# MRCS-Dual-3-Position-Semaphore-Controlle.net
KiCad netlist of a schematic drawn in EAGLE
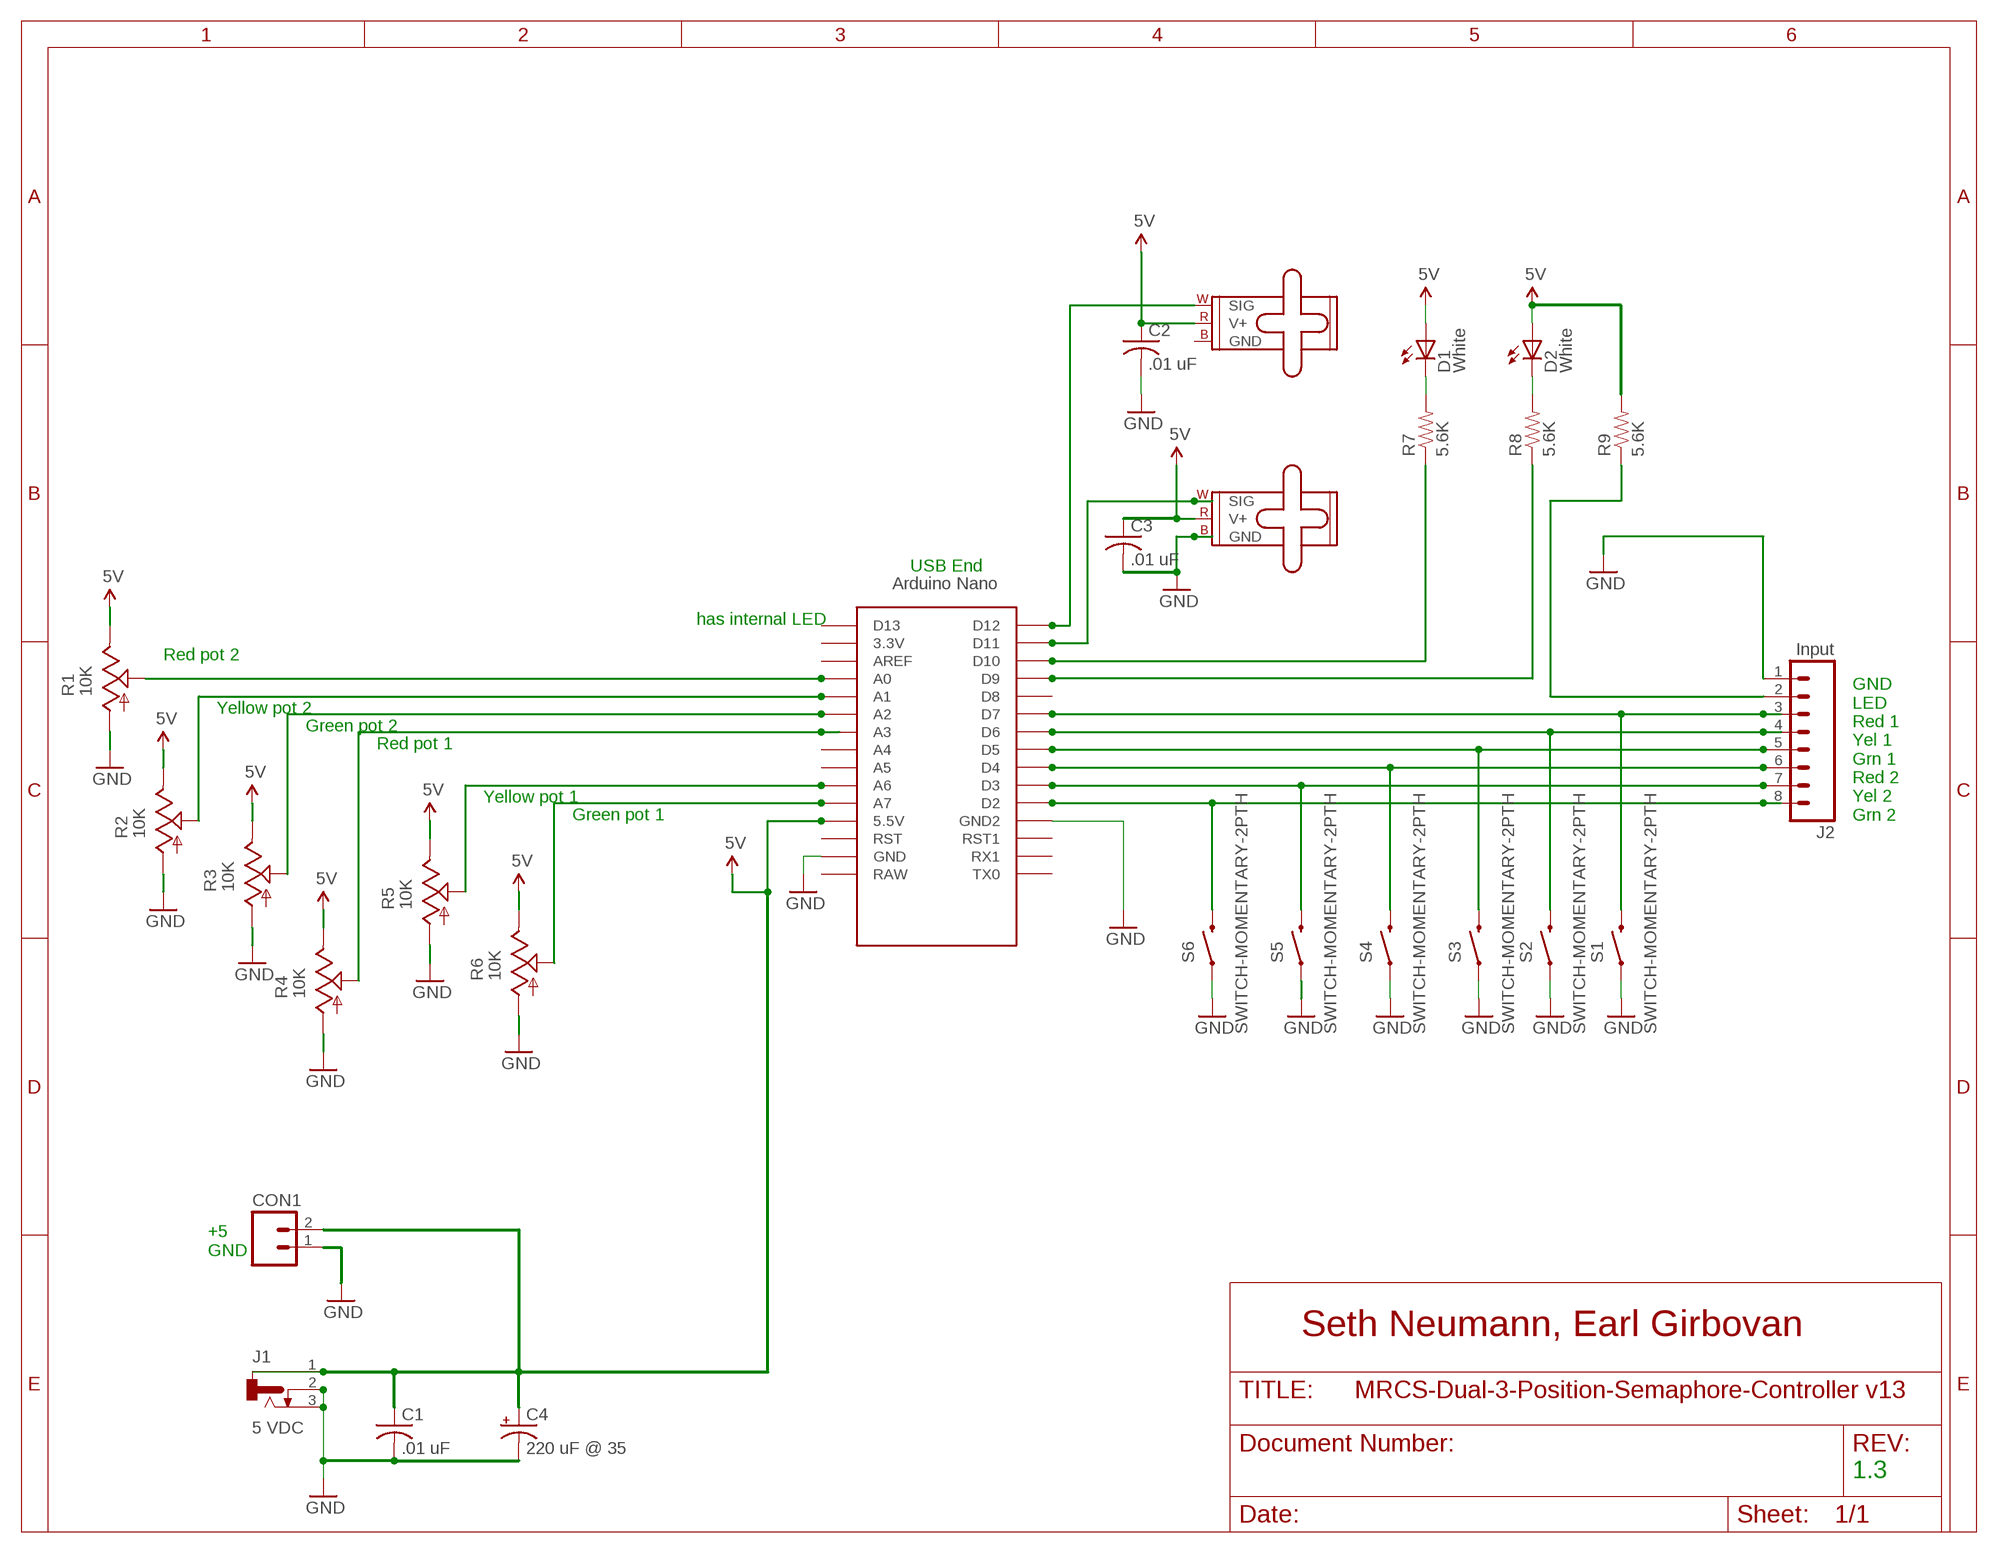
[diagram p0: schematic, sheet 1]

(export (version "E")
  (design (tool "Eeschema 10.0.6"))
  (components
    (comp (ref "C1")
      (value ".01 uF")
      (footprint "eagle-import:C050-024X044")
      (libsource (lib "eagle-import") (part "CAPPTH1"))
    )
    (comp (ref "C2")
      (value ".01 uF")
      (footprint "eagle-import:C050-024X044")
      (libsource (lib "eagle-import") (part "CAPPTH1"))
    )
    (comp (ref "C3")
      (value ".01 uF")
      (footprint "eagle-import:C050-024X044")
      (libsource (lib "eagle-import") (part "CAPPTH1"))
    )
    (comp (ref "C4")
      (value "220 uF @ 35")
      (footprint "eagle-import:E5-10.5")
      (libsource (lib "eagle-import") (part "CAP-POLPTH-5MM"))
    )
    (comp (ref "CON1")
      (value "CONNECTOR-M023.5MM-LOCK")
      (footprint "eagle-import:SCREWTERMINAL-3.5MM-2_LOCK")
      (libsource (lib "eagle-import") (part "CONNECTOR-M023.5MM-LOCK"))
    )
    (comp (ref "D1")
      (value "White")
      (footprint "eagle-import:LED3MM")
      (libsource (lib "eagle-import") (part "LEDLED3MM"))
    )
    (comp (ref "D2")
      (value "White")
      (footprint "eagle-import:LED3MM")
      (libsource (lib "eagle-import") (part "LEDLED3MM"))
    )
    (comp (ref "J1")
      (value "5 VDC")
      (footprint "eagle-import:DCJ0202")
      (libsource (lib "eagle-import") (part "CONNECTOR-DC-POWER-RA"))
    )
    (comp (ref "J2")
      (value "Input")
      (footprint "eagle-import:1X08_LOCK")
      (libsource (lib "eagle-import") (part "CONNECTOR-M08LOCK"))
    )
    (comp (ref "M1")
      (value "SMALL_SERVO")
      (footprint "eagle-import:1X03")
      (libsource (lib "eagle-import") (part "SMALL_SERVO"))
    )
    (comp (ref "M2")
      (value "SMALL_SERVO")
      (footprint "eagle-import:1X03")
      (libsource (lib "eagle-import") (part "SMALL_SERVO"))
    )
    (comp (ref "NANO")
      (value "NANO")
      (footprint "eagle-import:NANO")
      (libsource (lib "eagle-import") (part "NANO"))
    )
    (comp (ref "R1")
      (value "10K")
      (footprint "eagle-import:RS3")
      (libsource (lib "eagle-import") (part "TRIM_US-RS3"))
    )
    (comp (ref "R2")
      (value "10K")
      (footprint "eagle-import:RS3")
      (libsource (lib "eagle-import") (part "TRIM_US-RS3"))
    )
    (comp (ref "R3")
      (value "10K")
      (footprint "eagle-import:RS3")
      (libsource (lib "eagle-import") (part "TRIM_US-RS3"))
    )
    (comp (ref "R4")
      (value "10K")
      (footprint "eagle-import:RS3")
      (libsource (lib "eagle-import") (part "TRIM_US-RS3"))
    )
    (comp (ref "R5")
      (value "10K")
      (footprint "eagle-import:RS3")
      (libsource (lib "eagle-import") (part "TRIM_US-RS3"))
    )
    (comp (ref "R6")
      (value "10K")
      (footprint "eagle-import:RS3")
      (libsource (lib "eagle-import") (part "TRIM_US-RS3"))
    )
    (comp (ref "R7")
      (value "5.6K")
      (footprint "eagle-import:AXIAL-0.4")
      (libsource (lib "eagle-import") (part "RESISTORPTH-1/4W"))
    )
    (comp (ref "R8")
      (value "5.6K")
      (footprint "eagle-import:AXIAL-0.4")
      (libsource (lib "eagle-import") (part "RESISTORPTH-1/4W"))
    )
    (comp (ref "R9")
      (value "5.6K")
      (footprint "eagle-import:AXIAL-0.4")
      (libsource (lib "eagle-import") (part "RESISTORPTH-1/4W"))
    )
    (comp (ref "S1")
      (value "SWITCH-MOMENTARY-2PTH")
      (footprint "eagle-import:TACTILE-PTH")
      (libsource (lib "eagle-import") (part "SWITCH-MOMENTARY-2PTH"))
    )
    (comp (ref "S2")
      (value "SWITCH-MOMENTARY-2PTH")
      (footprint "eagle-import:TACTILE-PTH")
      (libsource (lib "eagle-import") (part "SWITCH-MOMENTARY-2PTH"))
    )
    (comp (ref "S3")
      (value "SWITCH-MOMENTARY-2PTH")
      (footprint "eagle-import:TACTILE-PTH")
      (libsource (lib "eagle-import") (part "SWITCH-MOMENTARY-2PTH"))
    )
    (comp (ref "S4")
      (value "SWITCH-MOMENTARY-2PTH")
      (footprint "eagle-import:TACTILE-PTH")
      (libsource (lib "eagle-import") (part "SWITCH-MOMENTARY-2PTH"))
    )
    (comp (ref "S5")
      (value "SWITCH-MOMENTARY-2PTH")
      (footprint "eagle-import:TACTILE-PTH")
      (libsource (lib "eagle-import") (part "SWITCH-MOMENTARY-2PTH"))
    )
    (comp (ref "S6")
      (value "SWITCH-MOMENTARY-2PTH")
      (footprint "eagle-import:TACTILE-PTH")
      (libsource (lib "eagle-import") (part "SWITCH-MOMENTARY-2PTH"))
    )
  )
  (nets
    (net (code "1") (name "5V") (class "Default")
      (node (ref "C1") (pin "1") (pinfunction "1_1") (pintype "passive"))
      (node (ref "C2") (pin "1") (pinfunction "1_1") (pintype "passive"))
      (node (ref "C3") (pin "1") (pinfunction "1_1") (pintype "passive"))
      (node (ref "C4") (pin "+") (pinfunction "+_+") (pintype "passive"))
      (node (ref "CON1") (pin "2") (pinfunction "B_2") (pintype "passive"))
      (node (ref "D1") (pin "A") (pinfunction "A_A") (pintype "passive"))
      (node (ref "D2") (pin "A") (pinfunction "A_A") (pintype "passive"))
      (node (ref "J1") (pin "1") (pinfunction "1_1") (pintype "passive"))
      (node (ref "M1") (pin "2") (pinfunction "V+_2") (pintype "bidirectional"))
      (node (ref "M2") (pin "2") (pinfunction "V+_2") (pintype "bidirectional"))
      (node (ref "NANO") (pin "5V") (pinfunction "5.5V_5V") (pintype "bidirectional"))
      (node (ref "R1") (pin "E") (pinfunction "E_E") (pintype "passive"))
      (node (ref "R2") (pin "E") (pinfunction "E_E") (pintype "passive"))
      (node (ref "R3") (pin "E") (pinfunction "E_E") (pintype "passive"))
      (node (ref "R4") (pin "E") (pinfunction "E_E") (pintype "passive"))
      (node (ref "R5") (pin "E") (pinfunction "E_E") (pintype "passive"))
      (node (ref "R6") (pin "E") (pinfunction "E_E") (pintype "passive"))
      (node (ref "R9") (pin "P$2") (pinfunction "2_P$2") (pintype "passive"))
    )
    (net (code "2") (name "GND") (class "Default")
      (node (ref "C1") (pin "2") (pinfunction "2_2") (pintype "passive"))
      (node (ref "C2") (pin "2") (pinfunction "2_2") (pintype "passive"))
      (node (ref "C3") (pin "2") (pinfunction "2_2") (pintype "passive"))
      (node (ref "C4") (pin "-") (pinfunction "-_-") (pintype "passive"))
      (node (ref "CON1") (pin "1") (pinfunction "A_1") (pintype "passive"))
      (node (ref "J1") (pin "2") (pinfunction "2_2") (pintype "passive"))
      (node (ref "J1") (pin "3") (pinfunction "3_3") (pintype "passive"))
      (node (ref "J2") (pin "1") (pinfunction "1_1") (pintype "passive"))
      (node (ref "M2") (pin "3") (pinfunction "GND_3") (pintype "bidirectional"))
      (node (ref "NANO") (pin "GND") (pinfunction "GND_GND") (pintype "bidirectional"))
      (node (ref "NANO") (pin "GND1") (pinfunction "GND2_GND1") (pintype "bidirectional"))
      (node (ref "R1") (pin "A") (pinfunction "A_A") (pintype "passive"))
      (node (ref "R2") (pin "A") (pinfunction "A_A") (pintype "passive"))
      (node (ref "R3") (pin "A") (pinfunction "A_A") (pintype "passive"))
      (node (ref "R4") (pin "A") (pinfunction "A_A") (pintype "passive"))
      (node (ref "R5") (pin "A") (pinfunction "A_A") (pintype "passive"))
      (node (ref "R6") (pin "A") (pinfunction "A_A") (pintype "passive"))
      (node (ref "S1") (pin "1") (pinfunction "1_1") (pintype "passive"))
      (node (ref "S2") (pin "1") (pinfunction "1_1") (pintype "passive"))
      (node (ref "S3") (pin "1") (pinfunction "1_1") (pintype "passive"))
      (node (ref "S4") (pin "1") (pinfunction "1_1") (pintype "passive"))
      (node (ref "S5") (pin "1") (pinfunction "1_1") (pintype "passive"))
      (node (ref "S6") (pin "1") (pinfunction "1_1") (pintype "passive"))
    )
    (net (code "3") (name "Net-(D1-C)") (class "Default")
      (node (ref "D1") (pin "K") (pinfunction "C_K") (pintype "passive"))
      (node (ref "R7") (pin "P$2") (pinfunction "2_P$2") (pintype "passive"))
    )
    (net (code "4") (name "Net-(D2-C)") (class "Default")
      (node (ref "D2") (pin "K") (pinfunction "C_K") (pintype "passive"))
      (node (ref "R8") (pin "P$2") (pinfunction "2_P$2") (pintype "passive"))
    )
    (net (code "5") (name "Net-(M1-SIG)") (class "Default")
      (node (ref "M1") (pin "1") (pinfunction "SIG_1") (pintype "bidirectional"))
      (node (ref "NANO") (pin "D12") (pinfunction "D12_D12") (pintype "bidirectional"))
    )
    (net (code "6") (name "Net-(M2-SIG)") (class "Default")
      (node (ref "M2") (pin "1") (pinfunction "SIG_1") (pintype "bidirectional"))
      (node (ref "NANO") (pin "D11") (pinfunction "D11_D11") (pintype "bidirectional"))
    )
    (net (code "7") (name "Net-(NANO-PadA0)") (class "Default")
      (node (ref "NANO") (pin "A0") (pinfunction "A0_A0") (pintype "bidirectional"))
      (node (ref "R1") (pin "S") (pinfunction "S_S") (pintype "passive"))
    )
    (net (code "8") (name "Net-(NANO-PadA1)") (class "Default")
      (node (ref "NANO") (pin "A1") (pinfunction "A1_A1") (pintype "bidirectional"))
      (node (ref "R2") (pin "S") (pinfunction "S_S") (pintype "passive"))
    )
    (net (code "9") (name "Net-(NANO-PadA2)") (class "Default")
      (node (ref "NANO") (pin "A2") (pinfunction "A2_A2") (pintype "bidirectional"))
      (node (ref "R3") (pin "S") (pinfunction "S_S") (pintype "passive"))
    )
    (net (code "10") (name "Net-(NANO-PadA3)") (class "Default")
      (node (ref "NANO") (pin "A3") (pinfunction "A3_A3") (pintype "bidirectional"))
      (node (ref "R4") (pin "S") (pinfunction "S_S") (pintype "passive"))
    )
    (net (code "11") (name "Net-(NANO-PadA6)") (class "Default")
      (node (ref "NANO") (pin "A6") (pinfunction "A6_A6") (pintype "bidirectional"))
      (node (ref "R5") (pin "S") (pinfunction "S_S") (pintype "passive"))
    )
    (net (code "12") (name "Net-(NANO-PadA7)") (class "Default")
      (node (ref "NANO") (pin "A7") (pinfunction "A7_A7") (pintype "bidirectional"))
      (node (ref "R6") (pin "S") (pinfunction "S_S") (pintype "passive"))
    )
    (net (code "13") (name "Net-(R7-1)") (class "Default")
      (node (ref "NANO") (pin "D10") (pinfunction "D10_D10") (pintype "bidirectional"))
      (node (ref "R7") (pin "P$1") (pinfunction "1_P$1") (pintype "passive"))
    )
    (net (code "14") (name "Net-(R8-1)") (class "Default")
      (node (ref "NANO") (pin "D9") (pinfunction "D9_D9") (pintype "bidirectional"))
      (node (ref "R8") (pin "P$1") (pinfunction "1_P$1") (pintype "passive"))
    )
    (net (code "15") (name "Net-(R9-1)") (class "Default")
      (node (ref "J2") (pin "2") (pinfunction "2_2") (pintype "passive"))
      (node (ref "R9") (pin "P$1") (pinfunction "1_P$1") (pintype "passive"))
    )
    (net (code "16") (name "Net-(S1-2)") (class "Default")
      (node (ref "J2") (pin "3") (pinfunction "3_3") (pintype "passive"))
      (node (ref "NANO") (pin "D7") (pinfunction "D7_D7") (pintype "bidirectional"))
      (node (ref "S1") (pin "3") (pinfunction "2_3") (pintype "passive"))
    )
    (net (code "17") (name "Net-(S2-2)") (class "Default")
      (node (ref "J2") (pin "4") (pinfunction "4_4") (pintype "passive"))
      (node (ref "NANO") (pin "D6") (pinfunction "D6_D6") (pintype "bidirectional"))
      (node (ref "S2") (pin "3") (pinfunction "2_3") (pintype "passive"))
    )
    (net (code "18") (name "Net-(S3-2)") (class "Default")
      (node (ref "J2") (pin "5") (pinfunction "5_5") (pintype "passive"))
      (node (ref "NANO") (pin "D5") (pinfunction "D5_D5") (pintype "bidirectional"))
      (node (ref "S3") (pin "3") (pinfunction "2_3") (pintype "passive"))
    )
    (net (code "19") (name "Net-(S4-2)") (class "Default")
      (node (ref "J2") (pin "6") (pinfunction "6_6") (pintype "passive"))
      (node (ref "NANO") (pin "D4") (pinfunction "D4_D4") (pintype "bidirectional"))
      (node (ref "S4") (pin "3") (pinfunction "2_3") (pintype "passive"))
    )
    (net (code "20") (name "Net-(S5-2)") (class "Default")
      (node (ref "J2") (pin "7") (pinfunction "7_7") (pintype "passive"))
      (node (ref "NANO") (pin "D3") (pinfunction "D3_D3") (pintype "bidirectional"))
      (node (ref "S5") (pin "3") (pinfunction "2_3") (pintype "passive"))
    )
    (net (code "21") (name "Net-(S6-2)") (class "Default")
      (node (ref "J2") (pin "8") (pinfunction "8_8") (pintype "passive"))
      (node (ref "NANO") (pin "D2") (pinfunction "D2_D2") (pintype "bidirectional"))
      (node (ref "S6") (pin "3") (pinfunction "2_3") (pintype "passive"))
    )
    (net (code "22") (name "unconnected-(M1-GND-Pad3)") (class "Default")
      (node (ref "M1") (pin "3") (pinfunction "GND_3") (pintype "bidirectional"))
    )
    (net (code "23") (name "unconnected-(NANO-Pad3.3V)") (class "Default")
      (node (ref "NANO") (pin "3.3V") (pinfunction "3.3V_3.3V") (pintype "bidirectional"))
    )
    (net (code "24") (name "unconnected-(NANO-PadA4)") (class "Default")
      (node (ref "NANO") (pin "A4") (pinfunction "A4_A4") (pintype "bidirectional"))
    )
    (net (code "25") (name "unconnected-(NANO-PadA5)") (class "Default")
      (node (ref "NANO") (pin "A5") (pinfunction "A5_A5") (pintype "bidirectional"))
    )
    (net (code "26") (name "unconnected-(NANO-PadAREF)") (class "Default")
      (node (ref "NANO") (pin "AREF") (pinfunction "AREF_AREF") (pintype "bidirectional"))
    )
    (net (code "27") (name "unconnected-(NANO-PadD8)") (class "Default")
      (node (ref "NANO") (pin "D8") (pinfunction "D8_D8") (pintype "bidirectional"))
    )
    (net (code "28") (name "unconnected-(NANO-PadD13)") (class "Default")
      (node (ref "NANO") (pin "D13") (pinfunction "D13_D13") (pintype "bidirectional"))
    )
    (net (code "29") (name "unconnected-(NANO-PadRAW)") (class "Default")
      (node (ref "NANO") (pin "RAW") (pinfunction "RAW_RAW") (pintype "bidirectional"))
    )
    (net (code "30") (name "unconnected-(NANO-PadRST)") (class "Default")
      (node (ref "NANO") (pin "RST") (pinfunction "RST_RST") (pintype "bidirectional"))
    )
    (net (code "31") (name "unconnected-(NANO-PadRST1)") (class "Default")
      (node (ref "NANO") (pin "RST1") (pinfunction "RST1_RST1") (pintype "bidirectional"))
    )
    (net (code "32") (name "unconnected-(NANO-PadRX1)") (class "Default")
      (node (ref "NANO") (pin "RX1") (pinfunction "RX1_RX1") (pintype "bidirectional"))
    )
    (net (code "33") (name "unconnected-(NANO-PadTX0)") (class "Default")
      (node (ref "NANO") (pin "TX0") (pinfunction "TX0_TX0") (pintype "bidirectional"))
    )
  )
)
